# Button_Decoding.net
KiCad netlist of a schematic drawn in Altium Designer
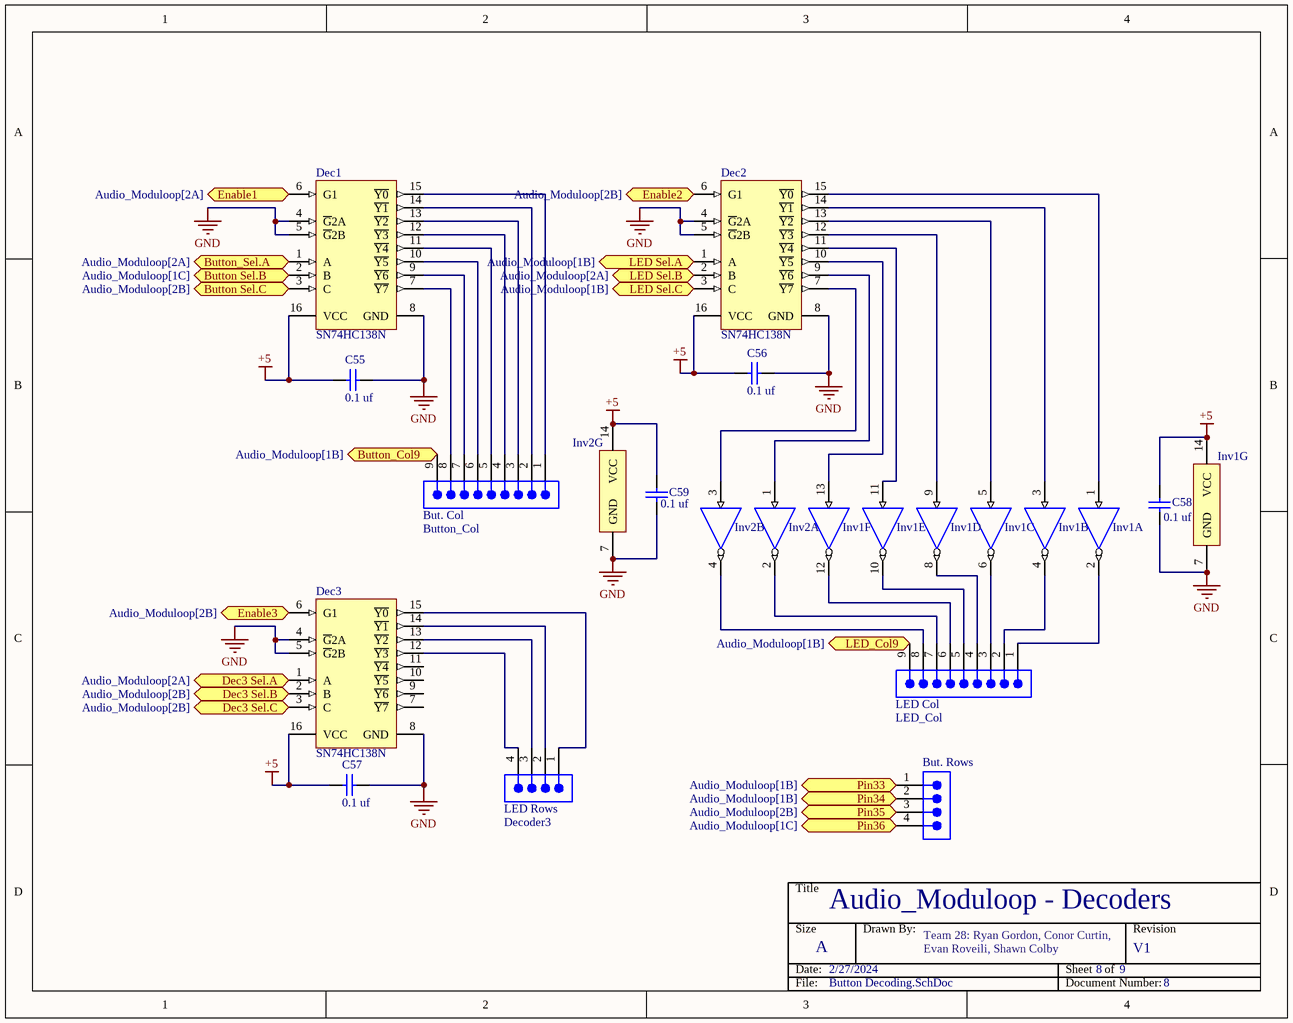
[diagram p0: Button Decoding.SchDoc]

(export (version "E")
  (design (tool "Eeschema 10.0.6"))
  (components
    (comp (ref "But. Col")
      (value "Button_Col")
      (footprint "61300911121")
      (libsource (lib "Altium Content Vault") (part "Header_Male_1R_09P"))
    )
    (comp (ref "But. Rows")
      (value "61300411121")
      (footprint "61300411121")
      (libsource (lib "Altium Content Vault") (part "Header_Male_1R_04P"))
    )
    (comp (ref "C55")
      (value "0.1 uf")
      (footprint "CAPC2013X135X45ML10T25")
      (description "Chip Capacitor, 0.1 uF, +/- 10%, 50 V, -55 to 125 degC, 0805 (2012 Metric), RoHS, Tape and Reel")
      (fields (field (name "VOLTAGE") "50V") (field (name "TOLERANCE") "10%"))
      (libsource (lib "Altium Content Vault") (part "CAP-NP-2"))
    )
    (comp (ref "C56")
      (value "0.1 uf")
      (footprint "CAPC2013X135X45ML10T25")
      (description "Chip Capacitor, 0.1 uF, +/- 10%, 50 V, -55 to 125 degC, 0805 (2012 Metric), RoHS, Tape and Reel")
      (fields (field (name "VOLTAGE") "50V") (field (name "TOLERANCE") "10%"))
      (libsource (lib "Altium Content Vault") (part "CAP-NP-2"))
    )
    (comp (ref "C57")
      (value "0.1 uf")
      (footprint "CAPC2013X135X45ML10T25")
      (description "Chip Capacitor, 0.1 uF, +/- 10%, 50 V, -55 to 125 degC, 0805 (2012 Metric), RoHS, Tape and Reel")
      (fields (field (name "VOLTAGE") "50V") (field (name "TOLERANCE") "10%"))
      (libsource (lib "Altium Content Vault") (part "CAP-NP-2"))
    )
    (comp (ref "C58")
      (value "0.1 uf")
      (footprint "CAPC2013X135X45ML10T25")
      (description "Chip Capacitor, 0.1 uF, +/- 10%, 50 V, -55 to 125 degC, 0805 (2012 Metric), RoHS, Tape and Reel")
      (fields (field (name "VOLTAGE") "50V") (field (name "TOLERANCE") "10%"))
      (libsource (lib "Altium Content Vault") (part "CAP-NP-2"))
    )
    (comp (ref "C59")
      (value "0.1 uf")
      (footprint "CAPC2013X135X45ML10T25")
      (description "Chip Capacitor, 0.1 uF, +/- 10%, 50 V, -55 to 125 degC, 0805 (2012 Metric), RoHS, Tape and Reel")
      (fields (field (name "VOLTAGE") "50V") (field (name "TOLERANCE") "10%"))
      (libsource (lib "Altium Content Vault") (part "CAP-NP-2"))
    )
    (comp (ref "Dec1")
      (value "SN74HC138N")
      (footprint "N0016A")
      (description "3-Line To 8-Line Decoders/Demultiplexers, N0016A, TUBE")
      (fields
        (field (name "MANUFACTURER") "Texas Instruments")
        (field (name "GENERIC PART NUMBER") "SN74HC138")
      )
      (libsource (lib "Altium Content Vault") (part "TI-SNX4XXXX138-16"))
    )
    (comp (ref "Dec2")
      (value "SN74HC138N")
      (footprint "N0016A")
      (description "3-Line To 8-Line Decoders/Demultiplexers, N0016A, TUBE")
      (fields
        (field (name "MANUFACTURER") "Texas Instruments")
        (field (name "GENERIC PART NUMBER") "SN74HC138")
      )
      (libsource (lib "Altium Content Vault") (part "TI-SNX4XXXX138-16"))
    )
    (comp (ref "Dec3")
      (value "SN74HC138N")
      (footprint "N0016A")
      (description "3-Line To 8-Line Decoders/Demultiplexers, N0016A, TUBE")
      (fields
        (field (name "MANUFACTURER") "Texas Instruments")
        (field (name "GENERIC PART NUMBER") "SN74HC138")
      )
      (libsource (lib "Altium Content Vault") (part "TI-SNX4XXXX138-16"))
    )
    (comp (ref "Inv1")
      (value "Inv1")
      (footprint "N0014A")
      (description "Hex Inverters, N0014A, TUBE")
      (fields
        (field (name "MANUFACTURER") "Texas Instruments")
        (field (name "GENERIC PART NUMBER") "SN74HC04")
      )
      (libsource (lib "Altium Content Vault") (part "TI-CD_SNX4XXXXXX4X_19A-14"))
    )
    (comp (ref "Inv2")
      (value "Inv2")
      (footprint "N0014A")
      (description "Hex Inverters, N0014A, TUBE")
      (fields
        (field (name "MANUFACTURER") "Texas Instruments")
        (field (name "GENERIC PART NUMBER") "SN74HC04")
      )
      (libsource (lib "Altium Content Vault") (part "TI-CD_SNX4XXXXXX4X_19A-14"))
    )
    (comp (ref "LED Col")
      (value "LED_Col")
      (footprint "61300911121")
      (libsource (lib "Altium Content Vault") (part "Header_Male_1R_09P"))
    )
    (comp (ref "LED Rows")
      (value "Decoder3")
      (footprint "61900411121")
      (libsource (lib "Altium Content Vault") (part "Header_Male_1R_04P"))
    )
  )
  (nets
    (net (code "1") (name "+5") (class "Default")
      (node (ref "C55") (pin "2") (pinfunction "2_2") (pintype "passive"))
      (node (ref "C56") (pin "2") (pinfunction "2_2") (pintype "passive"))
      (node (ref "C57") (pin "2") (pinfunction "2_2") (pintype "passive"))
      (node (ref "C58") (pin "1") (pinfunction "1_1") (pintype "passive"))
      (node (ref "C59") (pin "1") (pinfunction "1_1") (pintype "passive"))
      (node (ref "Dec1") (pin "16") (pinfunction "VCC_16") (pintype "power_in"))
      (node (ref "Dec2") (pin "16") (pinfunction "VCC_16") (pintype "power_in"))
      (node (ref "Dec3") (pin "16") (pinfunction "VCC_16") (pintype "power_in"))
      (node (ref "Inv1") (pin "14") (pinfunction "VCC_14") (pintype "power_in"))
      (node (ref "Inv2") (pin "14") (pinfunction "VCC_14") (pintype "power_in"))
    )
    (net (code "2") (name "/Button Sel.B") (class "Default")
      (node (ref "Dec1") (pin "2") (pinfunction "B_2") (pintype "input"))
    )
    (net (code "3") (name "/Button Sel.C") (class "Default")
      (node (ref "Dec1") (pin "3") (pinfunction "C_3") (pintype "input"))
    )
    (net (code "4") (name "/Button_Col9") (class "Default")
      (node (ref "But. Col") (pin "9") (pinfunction "9_9") (pintype "passive"))
    )
    (net (code "5") (name "/Button_Sel.A") (class "Default")
      (node (ref "Dec1") (pin "1") (pinfunction "A_1") (pintype "input"))
    )
    (net (code "6") (name "/Dec3 Sel.A") (class "Default")
      (node (ref "Dec3") (pin "1") (pinfunction "A_1") (pintype "input"))
    )
    (net (code "7") (name "/Dec3 Sel.B") (class "Default")
      (node (ref "Dec3") (pin "2") (pinfunction "B_2") (pintype "input"))
    )
    (net (code "8") (name "/Dec3 Sel.C") (class "Default")
      (node (ref "Dec3") (pin "3") (pinfunction "C_3") (pintype "input"))
    )
    (net (code "9") (name "/Enable1") (class "Default")
      (node (ref "Dec1") (pin "6") (pinfunction "G1_6") (pintype "input"))
    )
    (net (code "10") (name "/Enable2") (class "Default")
      (node (ref "Dec2") (pin "6") (pinfunction "G1_6") (pintype "input"))
    )
    (net (code "11") (name "/Enable3") (class "Default")
      (node (ref "Dec3") (pin "6") (pinfunction "G1_6") (pintype "input"))
    )
    (net (code "12") (name "/LED Sel.A") (class "Default")
      (node (ref "Dec2") (pin "1") (pinfunction "A_1") (pintype "input"))
    )
    (net (code "13") (name "/LED Sel.B") (class "Default")
      (node (ref "Dec2") (pin "2") (pinfunction "B_2") (pintype "input"))
    )
    (net (code "14") (name "/LED Sel.C") (class "Default")
      (node (ref "Dec2") (pin "3") (pinfunction "C_3") (pintype "input"))
    )
    (net (code "15") (name "/LED_Col9") (class "Default")
      (node (ref "LED Col") (pin "9") (pinfunction "9_9") (pintype "passive"))
    )
    (net (code "16") (name "/Pin33") (class "Default")
      (node (ref "But. Rows") (pin "1") (pinfunction "1_1") (pintype "passive"))
    )
    (net (code "17") (name "/Pin34") (class "Default")
      (node (ref "But. Rows") (pin "2") (pinfunction "2_2") (pintype "passive"))
    )
    (net (code "18") (name "/Pin35") (class "Default")
      (node (ref "But. Rows") (pin "3") (pinfunction "3_3") (pintype "passive"))
    )
    (net (code "19") (name "/Pin36") (class "Default")
      (node (ref "But. Rows") (pin "4") (pinfunction "4_4") (pintype "passive"))
    )
    (net (code "20") (name "GND") (class "Default")
      (node (ref "C55") (pin "1") (pinfunction "1_1") (pintype "passive"))
      (node (ref "C56") (pin "1") (pinfunction "1_1") (pintype "passive"))
      (node (ref "C57") (pin "1") (pinfunction "1_1") (pintype "passive"))
      (node (ref "C58") (pin "2") (pinfunction "2_2") (pintype "passive"))
      (node (ref "C59") (pin "2") (pinfunction "2_2") (pintype "passive"))
      (node (ref "Dec1") (pin "4") (pinfunction "~{G}2A_4") (pintype "input"))
      (node (ref "Dec1") (pin "5") (pinfunction "~{G}2B_5") (pintype "input"))
      (node (ref "Dec1") (pin "8") (pinfunction "GND_8") (pintype "power_in"))
      (node (ref "Dec2") (pin "4") (pinfunction "~{G}2A_4") (pintype "input"))
      (node (ref "Dec2") (pin "5") (pinfunction "~{G}2B_5") (pintype "input"))
      (node (ref "Dec2") (pin "8") (pinfunction "GND_8") (pintype "power_in"))
      (node (ref "Dec3") (pin "4") (pinfunction "~{G}2A_4") (pintype "input"))
      (node (ref "Dec3") (pin "5") (pinfunction "~{G}2B_5") (pintype "input"))
      (node (ref "Dec3") (pin "8") (pinfunction "GND_8") (pintype "power_in"))
      (node (ref "Inv1") (pin "7") (pinfunction "GND_7") (pintype "power_in"))
      (node (ref "Inv2") (pin "7") (pinfunction "GND_7") (pintype "power_in"))
    )
    (net (code "21") (name "Net-(Dec1-~{Y0})") (class "Default")
      (node (ref "But. Col") (pin "1") (pinfunction "1_1") (pintype "passive"))
      (node (ref "Dec1") (pin "15") (pinfunction "~{Y0}_15") (pintype "output"))
    )
    (net (code "22") (name "Net-(Dec1-~{Y1})") (class "Default")
      (node (ref "But. Col") (pin "2") (pinfunction "2_2") (pintype "passive"))
      (node (ref "Dec1") (pin "14") (pinfunction "~{Y1}_14") (pintype "output"))
    )
    (net (code "23") (name "Net-(Dec1-~{Y2})") (class "Default")
      (node (ref "But. Col") (pin "3") (pinfunction "3_3") (pintype "passive"))
      (node (ref "Dec1") (pin "13") (pinfunction "~{Y2}_13") (pintype "output"))
    )
    (net (code "24") (name "Net-(Dec1-~{Y3})") (class "Default")
      (node (ref "But. Col") (pin "4") (pinfunction "4_4") (pintype "passive"))
      (node (ref "Dec1") (pin "12") (pinfunction "~{Y3}_12") (pintype "output"))
    )
    (net (code "25") (name "Net-(Dec1-~{Y4})") (class "Default")
      (node (ref "But. Col") (pin "5") (pinfunction "5_5") (pintype "passive"))
      (node (ref "Dec1") (pin "11") (pinfunction "~{Y4}_11") (pintype "output"))
    )
    (net (code "26") (name "Net-(Dec1-~{Y5})") (class "Default")
      (node (ref "But. Col") (pin "6") (pinfunction "6_6") (pintype "passive"))
      (node (ref "Dec1") (pin "10") (pinfunction "~{Y5}_10") (pintype "output"))
    )
    (net (code "27") (name "Net-(Dec1-~{Y6})") (class "Default")
      (node (ref "But. Col") (pin "7") (pinfunction "7_7") (pintype "passive"))
      (node (ref "Dec1") (pin "9") (pinfunction "~{Y6}_9") (pintype "output"))
    )
    (net (code "28") (name "Net-(Dec1-~{Y7})") (class "Default")
      (node (ref "But. Col") (pin "8") (pinfunction "8_8") (pintype "passive"))
      (node (ref "Dec1") (pin "7") (pinfunction "~{Y7}_7") (pintype "output"))
    )
    (net (code "29") (name "Net-(Dec2-~{Y0})") (class "Default")
      (node (ref "Dec2") (pin "15") (pinfunction "~{Y0}_15") (pintype "output"))
      (node (ref "Inv1") (pin "1") (pinfunction "1A_1") (pintype "input"))
    )
    (net (code "30") (name "Net-(Dec2-~{Y1})") (class "Default")
      (node (ref "Dec2") (pin "14") (pinfunction "~{Y1}_14") (pintype "output"))
      (node (ref "Inv1") (pin "3") (pinfunction "2A_3") (pintype "input"))
    )
    (net (code "31") (name "Net-(Dec2-~{Y2})") (class "Default")
      (node (ref "Dec2") (pin "13") (pinfunction "~{Y2}_13") (pintype "output"))
      (node (ref "Inv1") (pin "5") (pinfunction "3A_5") (pintype "input"))
    )
    (net (code "32") (name "Net-(Dec2-~{Y3})") (class "Default")
      (node (ref "Dec2") (pin "12") (pinfunction "~{Y3}_12") (pintype "output"))
      (node (ref "Inv1") (pin "9") (pinfunction "4A_9") (pintype "input"))
    )
    (net (code "33") (name "Net-(Dec2-~{Y4})") (class "Default")
      (node (ref "Dec2") (pin "11") (pinfunction "~{Y4}_11") (pintype "output"))
      (node (ref "Inv1") (pin "11") (pinfunction "5A_11") (pintype "input"))
    )
    (net (code "34") (name "Net-(Dec2-~{Y5})") (class "Default")
      (node (ref "Dec2") (pin "10") (pinfunction "~{Y5}_10") (pintype "output"))
      (node (ref "Inv1") (pin "13") (pinfunction "6A_13") (pintype "input"))
    )
    (net (code "35") (name "Net-(Dec2-~{Y6})") (class "Default")
      (node (ref "Dec2") (pin "9") (pinfunction "~{Y6}_9") (pintype "output"))
      (node (ref "Inv2") (pin "1") (pinfunction "1A_1") (pintype "input"))
    )
    (net (code "36") (name "Net-(Dec2-~{Y7})") (class "Default")
      (node (ref "Dec2") (pin "7") (pinfunction "~{Y7}_7") (pintype "output"))
      (node (ref "Inv2") (pin "3") (pinfunction "2A_3") (pintype "input"))
    )
    (net (code "37") (name "Net-(Dec3-~{Y0})") (class "Default")
      (node (ref "Dec3") (pin "15") (pinfunction "~{Y0}_15") (pintype "output"))
      (node (ref "LED Rows") (pin "1") (pinfunction "1_1") (pintype "passive"))
    )
    (net (code "38") (name "Net-(Dec3-~{Y1})") (class "Default")
      (node (ref "Dec3") (pin "14") (pinfunction "~{Y1}_14") (pintype "output"))
      (node (ref "LED Rows") (pin "2") (pinfunction "2_2") (pintype "passive"))
    )
    (net (code "39") (name "Net-(Dec3-~{Y2})") (class "Default")
      (node (ref "Dec3") (pin "13") (pinfunction "~{Y2}_13") (pintype "output"))
      (node (ref "LED Rows") (pin "3") (pinfunction "3_3") (pintype "passive"))
    )
    (net (code "40") (name "Net-(Dec3-~{Y3})") (class "Default")
      (node (ref "Dec3") (pin "12") (pinfunction "~{Y3}_12") (pintype "output"))
      (node (ref "LED Rows") (pin "4") (pinfunction "4_4") (pintype "passive"))
    )
    (net (code "41") (name "Net-(Inv1A-~{1Y})") (class "Default")
      (node (ref "Inv1") (pin "2") (pinfunction "~{1Y}_2") (pintype "output"))
      (node (ref "LED Col") (pin "1") (pinfunction "1_1") (pintype "passive"))
    )
    (net (code "42") (name "Net-(Inv1B-~{2Y})") (class "Default")
      (node (ref "Inv1") (pin "4") (pinfunction "~{2Y}_4") (pintype "output"))
      (node (ref "LED Col") (pin "2") (pinfunction "2_2") (pintype "passive"))
    )
    (net (code "43") (name "Net-(Inv1C-~{3Y})") (class "Default")
      (node (ref "Inv1") (pin "6") (pinfunction "~{3Y}_6") (pintype "output"))
      (node (ref "LED Col") (pin "3") (pinfunction "3_3") (pintype "passive"))
    )
    (net (code "44") (name "Net-(Inv1D-~{4Y})") (class "Default")
      (node (ref "Inv1") (pin "8") (pinfunction "~{4Y}_8") (pintype "output"))
      (node (ref "LED Col") (pin "4") (pinfunction "4_4") (pintype "passive"))
    )
    (net (code "45") (name "Net-(Inv1E-~{5Y})") (class "Default")
      (node (ref "Inv1") (pin "10") (pinfunction "~{5Y}_10") (pintype "output"))
      (node (ref "LED Col") (pin "5") (pinfunction "5_5") (pintype "passive"))
    )
    (net (code "46") (name "Net-(Inv1F-~{6Y})") (class "Default")
      (node (ref "Inv1") (pin "12") (pinfunction "~{6Y}_12") (pintype "output"))
      (node (ref "LED Col") (pin "6") (pinfunction "6_6") (pintype "passive"))
    )
    (net (code "47") (name "Net-(Inv2A-~{1Y})") (class "Default")
      (node (ref "Inv2") (pin "2") (pinfunction "~{1Y}_2") (pintype "output"))
      (node (ref "LED Col") (pin "7") (pinfunction "7_7") (pintype "passive"))
    )
    (net (code "48") (name "Net-(Inv2B-~{2Y})") (class "Default")
      (node (ref "Inv2") (pin "4") (pinfunction "~{2Y}_4") (pintype "output"))
      (node (ref "LED Col") (pin "8") (pinfunction "8_8") (pintype "passive"))
    )
    (net (code "49") (name "unconnected-(Dec3-~{Y4}-Pad11)") (class "Default")
      (node (ref "Dec3") (pin "11") (pinfunction "~{Y4}_11") (pintype "output"))
    )
    (net (code "50") (name "unconnected-(Dec3-~{Y5}-Pad10)") (class "Default")
      (node (ref "Dec3") (pin "10") (pinfunction "~{Y5}_10") (pintype "output"))
    )
    (net (code "51") (name "unconnected-(Dec3-~{Y6}-Pad9)") (class "Default")
      (node (ref "Dec3") (pin "9") (pinfunction "~{Y6}_9") (pintype "output"))
    )
    (net (code "52") (name "unconnected-(Dec3-~{Y7}-Pad7)") (class "Default")
      (node (ref "Dec3") (pin "7") (pinfunction "~{Y7}_7") (pintype "output"))
    )
  )
)
